# AnalisisAC.net
KiCad netlist of a schematic drawn in Altium Designer
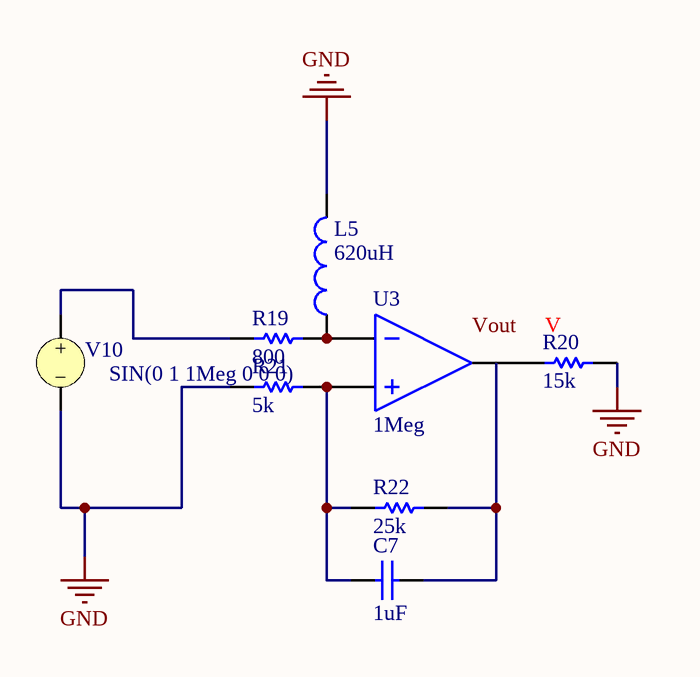
[diagram p0: AnalisisAC.SchDoc]

(export (version "E")
  (design (tool "Eeschema 10.0.6"))
  (components
    (comp (ref "C7")
      (value "1uF")
      (description "Capacitor")
      (libsource (lib "Simulation Generic Components") (part "Capacitor"))
    )
    (comp (ref "L5")
      (value "620uH")
      (description "Inductor")
      (libsource (lib "Simulation Generic Components") (part "Inductor"))
    )
    (comp (ref "R19")
      (value "800")
      (description "Resistor")
      (libsource (lib "Simulation Generic Components") (part "Resistor"))
    )
    (comp (ref "R20")
      (value "15k")
      (description "Resistor")
      (libsource (lib "Simulation Generic Components") (part "Resistor"))
    )
    (comp (ref "R21")
      (value "5k")
      (description "Resistor")
      (libsource (lib "Simulation Generic Components") (part "Resistor"))
    )
    (comp (ref "R22")
      (value "25k")
      (description "Resistor")
      (libsource (lib "Simulation Generic Components") (part "Resistor"))
    )
    (comp (ref "U3")
      (value "Ideal Operational Amplifier")
      (fields (field (name "GAIN") "1Meg"))
      (libsource (lib "Simulation Generic Components") (part "OpAmp"))
    )
    (comp (ref "V10")
      (value "SIN(0 1 1Meg 0 0 0)")
      (description "Voltage Source")
      (fields (field (name "PUBLISHER") "Altium Limited"))
      (libsource (lib "Simulation Generic Components") (part "VSRC"))
    )
  )
  (nets
    (net (code "2") (name "GND") (class "Default")
      (node (ref "L5") (pin "2") (pinfunction "2_2") (pintype "passive"))
      (node (ref "R20") (pin "2") (pinfunction "2_2") (pintype "passive"))
      (node (ref "R21") (pin "1") (pinfunction "1_1") (pintype "passive"))
      (node (ref "V10") (pin "2") (pinfunction "2_2") (pintype "passive"))
    )
    (net (code "3") (name "Net-(C7-Pad1)") (class "Default")
      (node (ref "C7") (pin "1") (pinfunction "1_1") (pintype "passive"))
      (node (ref "R22") (pin "2") (pinfunction "2_2") (pintype "passive"))
    )
    (net (code "4") (name "Net-(R19-Pad1)") (class "Default")
      (node (ref "R19") (pin "1") (pinfunction "1_1") (pintype "passive"))
      (node (ref "V10") (pin "1") (pinfunction "1_1") (pintype "passive"))
    )
    (net (code "5") (name "Net-(U3-IN+)") (class "Default")
      (node (ref "C7") (pin "2") (pinfunction "2_2") (pintype "passive"))
      (node (ref "R21") (pin "2") (pinfunction "2_2") (pintype "passive"))
      (node (ref "R22") (pin "1") (pinfunction "1_1") (pintype "passive"))
      (node (ref "U3") (pin "2") (pinfunction "IN+_2") (pintype "passive"))
    )
    (net (code "6") (name "Net-(U3-IN-)") (class "Default")
      (node (ref "L5") (pin "1") (pinfunction "1_1") (pintype "passive"))
      (node (ref "R19") (pin "2") (pinfunction "2_2") (pintype "passive"))
      (node (ref "U3") (pin "1") (pinfunction "IN-_1") (pintype "passive"))
    )
    (net (code "7") (name "Net-(U3-OUT)") (class "Default")
      (node (ref "R20") (pin "1") (pinfunction "1_1") (pintype "passive"))
      (node (ref "U3") (pin "3") (pinfunction "OUT_3") (pintype "passive"))
    )
  )
)
